# uC.net
KiCad netlist of a schematic drawn in Altium Designer
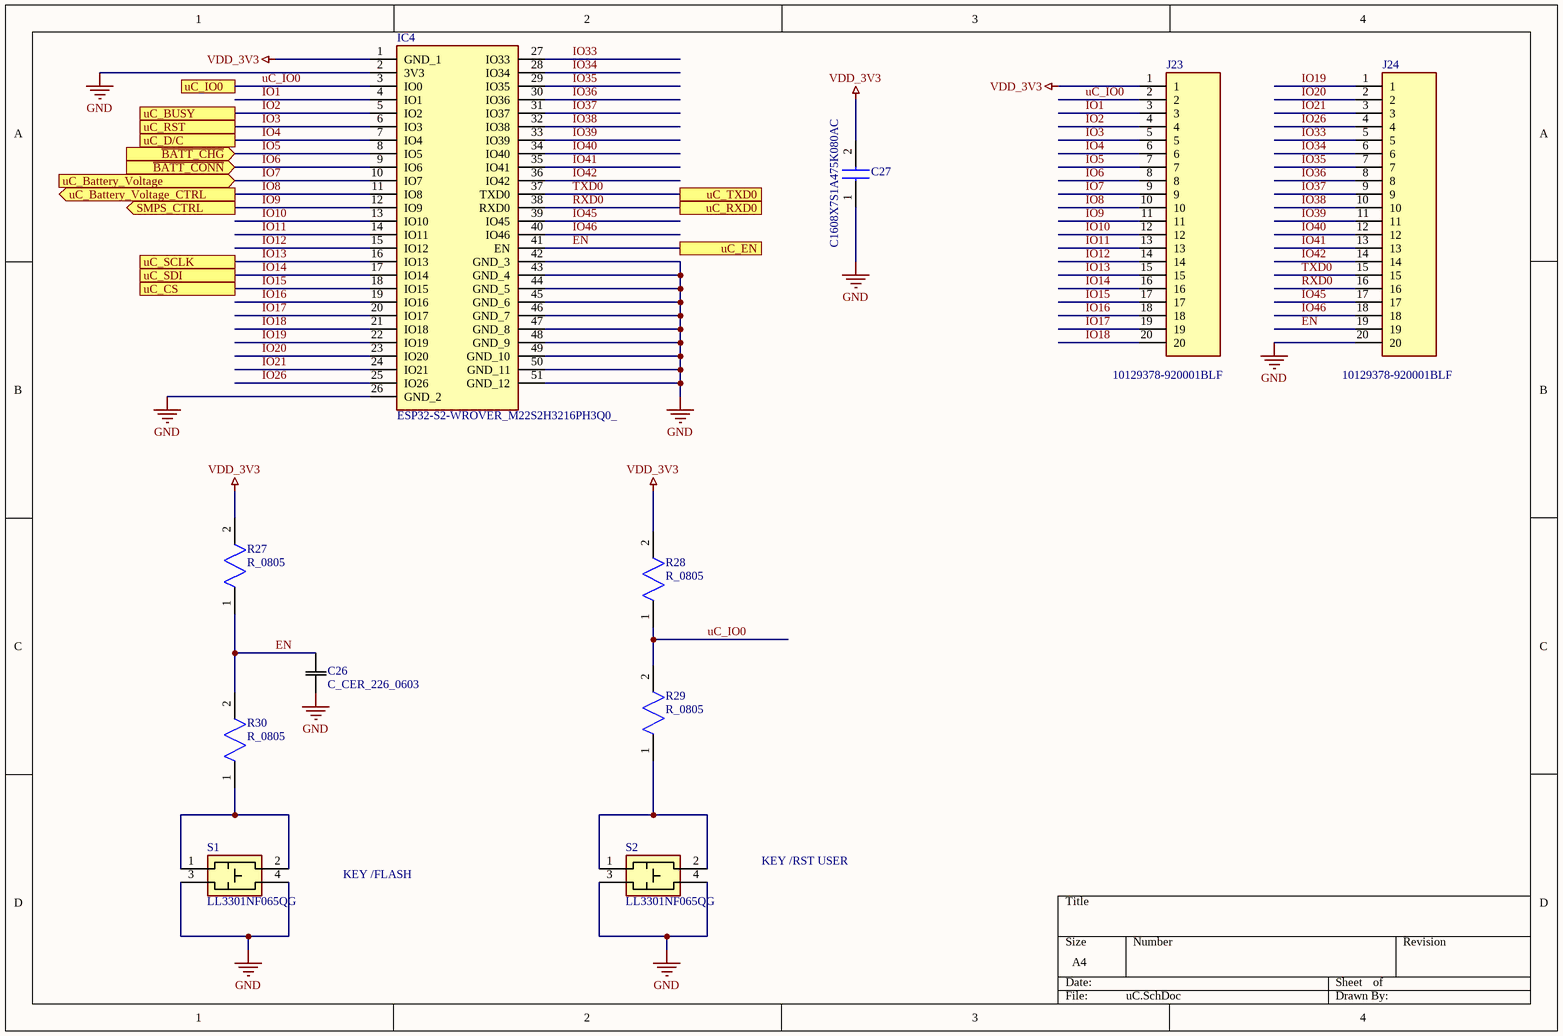
[diagram p0: uC.SchDoc]

(export (version "E")
  (design (tool "Eeschema 10.0.6"))
  (components
    (comp (ref "C26")
      (value "C_CER_226_0603")
      (footprint "CAPC1608X90N")
      (fields
        (field (name "MANUFACTURER_PART_NUMBER") "GRM188R60J226MEA0D")
        (field (name "COPYRIGHT") "Copyright (C) 2015 Accelerated Designs. All rights reserved")
      )
      (libsource (lib "Main") (part "C_CER_226_0603"))
    )
    (comp (ref "C27")
      (value "C1608X7S1A475K080AC")
      (footprint "SamacSys:CAPC1608X90N")
      (description "Capacitor")
      (libsource (lib "Main") (part "C1608X7S1A475K080AC"))
    )
    (comp (ref "IC4")
      (value "ESP32-S2-WROVER_M22S2H3216PH3Q0_")
      (footprint "SamacSys:ESP32S2WROVERM22S2H3216PH3Q0")
      (description "Integrated Circuit")
      (fields (field (name "MANUFACTURER_PART_NUMBER") "ESP32-S2-WROVER(M22S2H3216PH3Q0)"))
      (libsource (lib "Main") (part "ESP32-S2-WROVER_M22S2H3216PH3Q0_"))
    )
    (comp (ref "J23")
      (value "10129378-920001BLF")
      (footprint "SamacSys:HDRV20W67P0X254_1X20_5080X241X858P")
      (description "Connector")
      (libsource (lib "Main") (part "10129378-920001BLF"))
    )
    (comp (ref "J24")
      (value "10129378-920001BLF")
      (footprint "SamacSys:HDRV20W67P0X254_1X20_5080X241X858P")
      (description "Connector")
      (libsource (lib "Main") (part "10129378-920001BLF"))
    )
    (comp (ref "R27")
      (value "R_0805")
      (footprint "RESC2012X55N")
      (description "Resistor")
      (libsource (lib "Main") (part "R_0805"))
    )
    (comp (ref "R28")
      (value "R_0805")
      (footprint "RESC2012X55N")
      (description "Resistor")
      (libsource (lib "Main") (part "R_0805"))
    )
    (comp (ref "R29")
      (value "R_0805")
      (footprint "RESC2012X55N")
      (description "Resistor")
      (libsource (lib "Main") (part "R_0805"))
    )
    (comp (ref "R30")
      (value "R_0805")
      (footprint "RESC2012X55N")
      (description "Resistor")
      (libsource (lib "Main") (part "R_0805"))
    )
    (comp (ref "S1")
      (value "LL3301NF065QG")
      (footprint "SamacSys:LL3301NF065QG")
      (description "Switch")
      (fields (field (name "MOUSER2 PART NUMBER") "612-LL3301NF065QG"))
      (libsource (lib "Main") (part "LL3301NF065QG"))
    )
    (comp (ref "S2")
      (value "LL3301NF065QG")
      (footprint "SamacSys:LL3301NF065QG")
      (description "Switch")
      (fields (field (name "MOUSER2 PART NUMBER") "612-LL3301NF065QG"))
      (libsource (lib "Main") (part "LL3301NF065QG"))
    )
  )
  (nets
    (net (code "1") (name "/EN") (class "Default")
      (node (ref "C26") (pin "2") (pinfunction "2_2") (pintype "passive"))
      (node (ref "IC4") (pin "41") (pinfunction "EN_41") (pintype "passive"))
      (node (ref "J24") (pin "19") (pinfunction "19_19") (pintype "passive"))
      (node (ref "R27") (pin "1") (pinfunction "1_1") (pintype "passive"))
      (node (ref "R30") (pin "2") (pinfunction "2_2") (pintype "passive"))
    )
    (net (code "2") (name "/IO1") (class "Default")
      (node (ref "IC4") (pin "4") (pinfunction "IO1_4") (pintype "passive"))
      (node (ref "J23") (pin "3") (pinfunction "3_3") (pintype "passive"))
    )
    (net (code "3") (name "/IO2") (class "Default")
      (node (ref "IC4") (pin "5") (pinfunction "IO2_5") (pintype "passive"))
      (node (ref "J23") (pin "4") (pinfunction "4_4") (pintype "passive"))
    )
    (net (code "4") (name "/IO3") (class "Default")
      (node (ref "IC4") (pin "6") (pinfunction "IO3_6") (pintype "passive"))
      (node (ref "J23") (pin "5") (pinfunction "5_5") (pintype "passive"))
    )
    (net (code "5") (name "/IO4") (class "Default")
      (node (ref "IC4") (pin "7") (pinfunction "IO4_7") (pintype "passive"))
      (node (ref "J23") (pin "6") (pinfunction "6_6") (pintype "passive"))
    )
    (net (code "6") (name "/IO5") (class "Default")
      (node (ref "IC4") (pin "8") (pinfunction "IO5_8") (pintype "passive"))
      (node (ref "J23") (pin "7") (pinfunction "7_7") (pintype "passive"))
    )
    (net (code "7") (name "/IO6") (class "Default")
      (node (ref "IC4") (pin "9") (pinfunction "IO6_9") (pintype "passive"))
      (node (ref "J23") (pin "8") (pinfunction "8_8") (pintype "passive"))
    )
    (net (code "8") (name "/IO7") (class "Default")
      (node (ref "IC4") (pin "10") (pinfunction "IO7_10") (pintype "passive"))
      (node (ref "J23") (pin "9") (pinfunction "9_9") (pintype "passive"))
    )
    (net (code "9") (name "/IO8") (class "Default")
      (node (ref "IC4") (pin "11") (pinfunction "IO8_11") (pintype "passive"))
      (node (ref "J23") (pin "10") (pinfunction "10_10") (pintype "passive"))
    )
    (net (code "10") (name "/IO9") (class "Default")
      (node (ref "IC4") (pin "12") (pinfunction "IO9_12") (pintype "passive"))
      (node (ref "J23") (pin "11") (pinfunction "11_11") (pintype "passive"))
    )
    (net (code "11") (name "/IO10") (class "Default")
      (node (ref "IC4") (pin "13") (pinfunction "IO10_13") (pintype "passive"))
      (node (ref "J23") (pin "12") (pinfunction "12_12") (pintype "passive"))
    )
    (net (code "12") (name "/IO11") (class "Default")
      (node (ref "IC4") (pin "14") (pinfunction "IO11_14") (pintype "passive"))
      (node (ref "J23") (pin "13") (pinfunction "13_13") (pintype "passive"))
    )
    (net (code "13") (name "/IO12") (class "Default")
      (node (ref "IC4") (pin "15") (pinfunction "IO12_15") (pintype "passive"))
      (node (ref "J23") (pin "14") (pinfunction "14_14") (pintype "passive"))
    )
    (net (code "14") (name "/IO13") (class "Default")
      (node (ref "IC4") (pin "16") (pinfunction "IO13_16") (pintype "passive"))
      (node (ref "J23") (pin "15") (pinfunction "15_15") (pintype "passive"))
    )
    (net (code "15") (name "/IO14") (class "Default")
      (node (ref "IC4") (pin "17") (pinfunction "IO14_17") (pintype "passive"))
      (node (ref "J23") (pin "16") (pinfunction "16_16") (pintype "passive"))
    )
    (net (code "16") (name "/IO15") (class "Default")
      (node (ref "IC4") (pin "18") (pinfunction "IO15_18") (pintype "passive"))
      (node (ref "J23") (pin "17") (pinfunction "17_17") (pintype "passive"))
    )
    (net (code "17") (name "/IO16") (class "Default")
      (node (ref "IC4") (pin "19") (pinfunction "IO16_19") (pintype "passive"))
      (node (ref "J23") (pin "18") (pinfunction "18_18") (pintype "passive"))
    )
    (net (code "18") (name "/IO17") (class "Default")
      (node (ref "IC4") (pin "20") (pinfunction "IO17_20") (pintype "passive"))
      (node (ref "J23") (pin "19") (pinfunction "19_19") (pintype "passive"))
    )
    (net (code "19") (name "/IO18") (class "Default")
      (node (ref "IC4") (pin "21") (pinfunction "IO18_21") (pintype "passive"))
      (node (ref "J23") (pin "20") (pinfunction "20_20") (pintype "passive"))
    )
    (net (code "20") (name "/IO19") (class "Default")
      (node (ref "IC4") (pin "22") (pinfunction "IO19_22") (pintype "passive"))
      (node (ref "J24") (pin "1") (pinfunction "1_1") (pintype "passive"))
    )
    (net (code "21") (name "/IO20") (class "Default")
      (node (ref "IC4") (pin "23") (pinfunction "IO20_23") (pintype "passive"))
      (node (ref "J24") (pin "2") (pinfunction "2_2") (pintype "passive"))
    )
    (net (code "22") (name "/IO21") (class "Default")
      (node (ref "IC4") (pin "24") (pinfunction "IO21_24") (pintype "passive"))
      (node (ref "J24") (pin "3") (pinfunction "3_3") (pintype "passive"))
    )
    (net (code "23") (name "/IO26") (class "Default")
      (node (ref "IC4") (pin "25") (pinfunction "IO26_25") (pintype "passive"))
      (node (ref "J24") (pin "4") (pinfunction "4_4") (pintype "passive"))
    )
    (net (code "24") (name "/IO33") (class "Default")
      (node (ref "IC4") (pin "27") (pinfunction "IO33_27") (pintype "passive"))
      (node (ref "J24") (pin "5") (pinfunction "5_5") (pintype "passive"))
    )
    (net (code "25") (name "/IO34") (class "Default")
      (node (ref "IC4") (pin "28") (pinfunction "IO34_28") (pintype "passive"))
      (node (ref "J24") (pin "6") (pinfunction "6_6") (pintype "passive"))
    )
    (net (code "26") (name "/IO35") (class "Default")
      (node (ref "IC4") (pin "29") (pinfunction "IO35_29") (pintype "passive"))
      (node (ref "J24") (pin "7") (pinfunction "7_7") (pintype "passive"))
    )
    (net (code "27") (name "/IO36") (class "Default")
      (node (ref "IC4") (pin "30") (pinfunction "IO36_30") (pintype "passive"))
      (node (ref "J24") (pin "8") (pinfunction "8_8") (pintype "passive"))
    )
    (net (code "28") (name "/IO37") (class "Default")
      (node (ref "IC4") (pin "31") (pinfunction "IO37_31") (pintype "passive"))
      (node (ref "J24") (pin "9") (pinfunction "9_9") (pintype "passive"))
    )
    (net (code "29") (name "/IO38") (class "Default")
      (node (ref "IC4") (pin "32") (pinfunction "IO38_32") (pintype "passive"))
      (node (ref "J24") (pin "10") (pinfunction "10_10") (pintype "passive"))
    )
    (net (code "30") (name "/IO39") (class "Default")
      (node (ref "IC4") (pin "33") (pinfunction "IO39_33") (pintype "passive"))
      (node (ref "J24") (pin "11") (pinfunction "11_11") (pintype "passive"))
    )
    (net (code "31") (name "/IO40") (class "Default")
      (node (ref "IC4") (pin "34") (pinfunction "IO40_34") (pintype "passive"))
      (node (ref "J24") (pin "12") (pinfunction "12_12") (pintype "passive"))
    )
    (net (code "32") (name "/IO41") (class "Default")
      (node (ref "IC4") (pin "35") (pinfunction "IO41_35") (pintype "passive"))
      (node (ref "J24") (pin "13") (pinfunction "13_13") (pintype "passive"))
    )
    (net (code "33") (name "/IO42") (class "Default")
      (node (ref "IC4") (pin "36") (pinfunction "IO42_36") (pintype "passive"))
      (node (ref "J24") (pin "14") (pinfunction "14_14") (pintype "passive"))
    )
    (net (code "34") (name "/IO45") (class "Default")
      (node (ref "IC4") (pin "39") (pinfunction "IO45_39") (pintype "passive"))
      (node (ref "J24") (pin "17") (pinfunction "17_17") (pintype "passive"))
    )
    (net (code "35") (name "/IO46") (class "Default")
      (node (ref "IC4") (pin "40") (pinfunction "IO46_40") (pintype "passive"))
      (node (ref "J24") (pin "18") (pinfunction "18_18") (pintype "passive"))
    )
    (net (code "36") (name "/RXD0") (class "Default")
      (node (ref "IC4") (pin "38") (pinfunction "RXD0_38") (pintype "passive"))
      (node (ref "J24") (pin "16") (pinfunction "16_16") (pintype "passive"))
    )
    (net (code "37") (name "/TXD0") (class "Default")
      (node (ref "IC4") (pin "37") (pinfunction "TXD0_37") (pintype "passive"))
      (node (ref "J24") (pin "15") (pinfunction "15_15") (pintype "passive"))
    )
    (net (code "38") (name "/uC_IO0") (class "Default")
      (node (ref "IC4") (pin "3") (pinfunction "IO0_3") (pintype "passive"))
      (node (ref "J23") (pin "2") (pinfunction "2_2") (pintype "passive"))
      (node (ref "R28") (pin "1") (pinfunction "1_1") (pintype "passive"))
      (node (ref "R29") (pin "2") (pinfunction "2_2") (pintype "passive"))
    )
    (net (code "39") (name "GND") (class "Default")
      (node (ref "C26") (pin "1") (pinfunction "1_1") (pintype "passive"))
      (node (ref "C27") (pin "1") (pinfunction "1_1") (pintype "passive"))
      (node (ref "IC4") (pin "2") (pinfunction "3V3_2") (pintype "passive"))
      (node (ref "IC4") (pin "26") (pinfunction "GND_2_26") (pintype "passive"))
      (node (ref "IC4") (pin "42") (pinfunction "GND_3_42") (pintype "passive"))
      (node (ref "IC4") (pin "43") (pinfunction "GND_4_43") (pintype "passive"))
      (node (ref "IC4") (pin "44") (pinfunction "GND_5_44") (pintype "passive"))
      (node (ref "IC4") (pin "45") (pinfunction "GND_6_45") (pintype "passive"))
      (node (ref "IC4") (pin "46") (pinfunction "GND_7_46") (pintype "passive"))
      (node (ref "IC4") (pin "47") (pinfunction "GND_8_47") (pintype "passive"))
      (node (ref "IC4") (pin "48") (pinfunction "GND_9_48") (pintype "passive"))
      (node (ref "IC4") (pin "49") (pinfunction "GND_10_49") (pintype "passive"))
      (node (ref "IC4") (pin "50") (pinfunction "GND_11_50") (pintype "passive"))
      (node (ref "IC4") (pin "51") (pinfunction "GND_12_51") (pintype "passive"))
      (node (ref "J24") (pin "20") (pinfunction "20_20") (pintype "passive"))
      (node (ref "S1") (pin "3") (pintype "passive"))
      (node (ref "S1") (pin "4") (pintype "passive"))
      (node (ref "S2") (pin "3") (pintype "passive"))
      (node (ref "S2") (pin "4") (pintype "passive"))
    )
    (net (code "40") (name "Net-(R29-Pad1)") (class "Default")
      (node (ref "R29") (pin "1") (pinfunction "1_1") (pintype "passive"))
      (node (ref "S2") (pin "1") (pintype "passive"))
      (node (ref "S2") (pin "2") (pintype "passive"))
    )
    (net (code "41") (name "Net-(R30-Pad1)") (class "Default")
      (node (ref "R30") (pin "1") (pinfunction "1_1") (pintype "passive"))
      (node (ref "S1") (pin "1") (pintype "passive"))
      (node (ref "S1") (pin "2") (pintype "passive"))
    )
    (net (code "42") (name "VDD_3V3") (class "Default")
      (node (ref "C27") (pin "2") (pinfunction "2_2") (pintype "passive"))
      (node (ref "IC4") (pin "1") (pinfunction "GND_1_1") (pintype "passive"))
      (node (ref "J23") (pin "1") (pinfunction "1_1") (pintype "passive"))
      (node (ref "R27") (pin "2") (pinfunction "2_2") (pintype "passive"))
      (node (ref "R28") (pin "2") (pinfunction "2_2") (pintype "passive"))
    )
  )
)
